# Analog_Input_Signal_Conditioning.net
KiCad netlist of a schematic drawn in Altium Designer
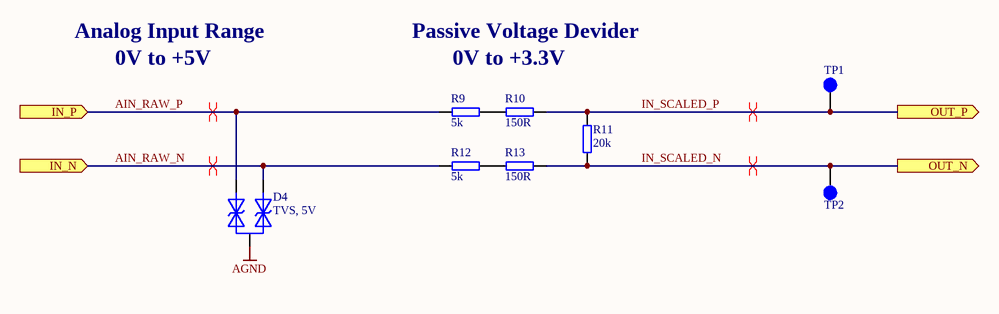
[diagram p0: Analog_Input_Signal_Conditioning.SchDoc]

(export (version "E")
  (design (tool "Eeschema 10.0.6"))
  (components
    (comp (ref "D4")
      (value "TVS, 5V")
      (footprint "SOT-23-3")
      (description "2-Line Bi-directional TVS Diode Array")
      (fields
        (field (name "MANUFACTURER PART NUMBER") "SMC05")
        (field (name "MANUFACTURER") "Leditech")
        (field (name "CREATED FROM") "AGeiger")
      )
      (libsource (lib "user") (part "TVS_BI_2_CH"))
    )
    (comp (ref "R9")
      (value "5k")
      (footprint "RES 0603_1608")
      (description "1/10W Thick Film Resistors 75V ±1% ±100ppm/℃ -55℃~+155℃ 5kΩ")
      (fields
        (field (name "MANUFACTURER PART NUMBER") "RTT035001FTP")
        (field (name "MANUFACTURER") "RALEC")
        (field (name "CREATED FROM") "AGeiger")
      )
      (libsource (lib "user") (part "Resistor"))
    )
    (comp (ref "R10")
      (value "150R")
      (footprint "RES 0603_1608")
      (description "100mW Thick Film Resistors 75V ±100ppm/℃ ±1% -55℃~+155℃ 150Ω")
      (fields
        (field (name "MANUFACTURER PART NUMBER") "0603WAF1500T5E")
        (field (name "MANUFACTURER") "UNI-ROYAL")
        (field (name "CREATED FROM") "AGeiger")
      )
      (libsource (lib "user") (part "Resistor"))
    )
    (comp (ref "R11")
      (value "20k")
      (footprint "RES 0603_1608")
      (description "SMD resistor E24 series")
      (fields
        (field (name "MANUFACTURER PART NUMBER") "0603WAF2002T5E")
        (field (name "MANUFACTURER") "UNI-ROYAL")
        (field (name "CREATED FROM") "AGeiger")
      )
      (libsource (lib "user") (part "Resistor"))
    )
    (comp (ref "R12")
      (value "5k")
      (footprint "RES 0603_1608")
      (description "1/10W Thick Film Resistors 75V ±1% ±100ppm/℃ -55℃~+155℃ 5kΩ")
      (fields
        (field (name "MANUFACTURER PART NUMBER") "RTT035001FTP")
        (field (name "MANUFACTURER") "RALEC")
        (field (name "CREATED FROM") "AGeiger")
      )
      (libsource (lib "user") (part "Resistor"))
    )
    (comp (ref "R13")
      (value "150R")
      (footprint "RES 0603_1608")
      (description "100mW Thick Film Resistors 75V ±100ppm/℃ ±1% -55℃~+155℃ 150Ω")
      (fields
        (field (name "MANUFACTURER PART NUMBER") "0603WAF1500T5E")
        (field (name "MANUFACTURER") "UNI-ROYAL")
        (field (name "CREATED FROM") "AGeiger")
      )
      (libsource (lib "user") (part "Resistor"))
    )
    (comp (ref "TP1")
      (value "Testpoint 1mm")
      (footprint "TP_1mm")
      (fields
        (field (name "MANUFACTURER PART NUMBER") "NULL")
        (field (name "CREATED") "2018_06_25_AGeiger")
        (field (name "CREATED FROM") "AGeiger")
      )
      (libsource (lib "user") (part "TP_1mm"))
    )
    (comp (ref "TP2")
      (value "Testpoint 1mm")
      (footprint "TP_1mm")
      (fields
        (field (name "MANUFACTURER PART NUMBER") "NULL")
        (field (name "CREATED") "2018_06_25_AGeiger")
        (field (name "CREATED FROM") "AGeiger")
      )
      (libsource (lib "user") (part "TP_1mm"))
    )
  )
  (nets
    (net (code "1") (name "/AIN_RAW_N") (class "Default")
      (node (ref "D4") (pin "1") (pinfunction "K1_1") (pintype "passive"))
      (node (ref "R12") (pin "1") (pinfunction "1_1") (pintype "passive"))
    )
    (net (code "2") (name "/AIN_RAW_P") (class "Default")
      (node (ref "D4") (pin "2") (pinfunction "K2_2") (pintype "passive"))
      (node (ref "R9") (pin "1") (pinfunction "1_1") (pintype "passive"))
    )
    (net (code "3") (name "/IN_SCALED_N") (class "Default")
      (node (ref "R11") (pin "1") (pinfunction "1_1") (pintype "passive"))
      (node (ref "R13") (pin "2") (pinfunction "2_2") (pintype "passive"))
      (node (ref "TP2") (pin "1") (pintype "passive"))
    )
    (net (code "4") (name "/IN_SCALED_P") (class "Default")
      (node (ref "R10") (pin "2") (pinfunction "2_2") (pintype "passive"))
      (node (ref "R11") (pin "2") (pinfunction "2_2") (pintype "passive"))
      (node (ref "TP1") (pin "1") (pintype "passive"))
    )
    (net (code "5") (name "AGND") (class "Default")
      (node (ref "D4") (pin "3") (pinfunction "A_3") (pintype "passive"))
    )
    (net (code "6") (name "Net-(R10-Pad1)") (class "Default")
      (node (ref "R10") (pin "1") (pinfunction "1_1") (pintype "passive"))
      (node (ref "R9") (pin "2") (pinfunction "2_2") (pintype "passive"))
    )
    (net (code "7") (name "Net-(R12-Pad2)") (class "Default")
      (node (ref "R12") (pin "2") (pinfunction "2_2") (pintype "passive"))
      (node (ref "R13") (pin "1") (pinfunction "1_1") (pintype "passive"))
    )
  )
)
